# B_PITCHROLLER.net
KiCad netlist of a schematic drawn in Altium Designer
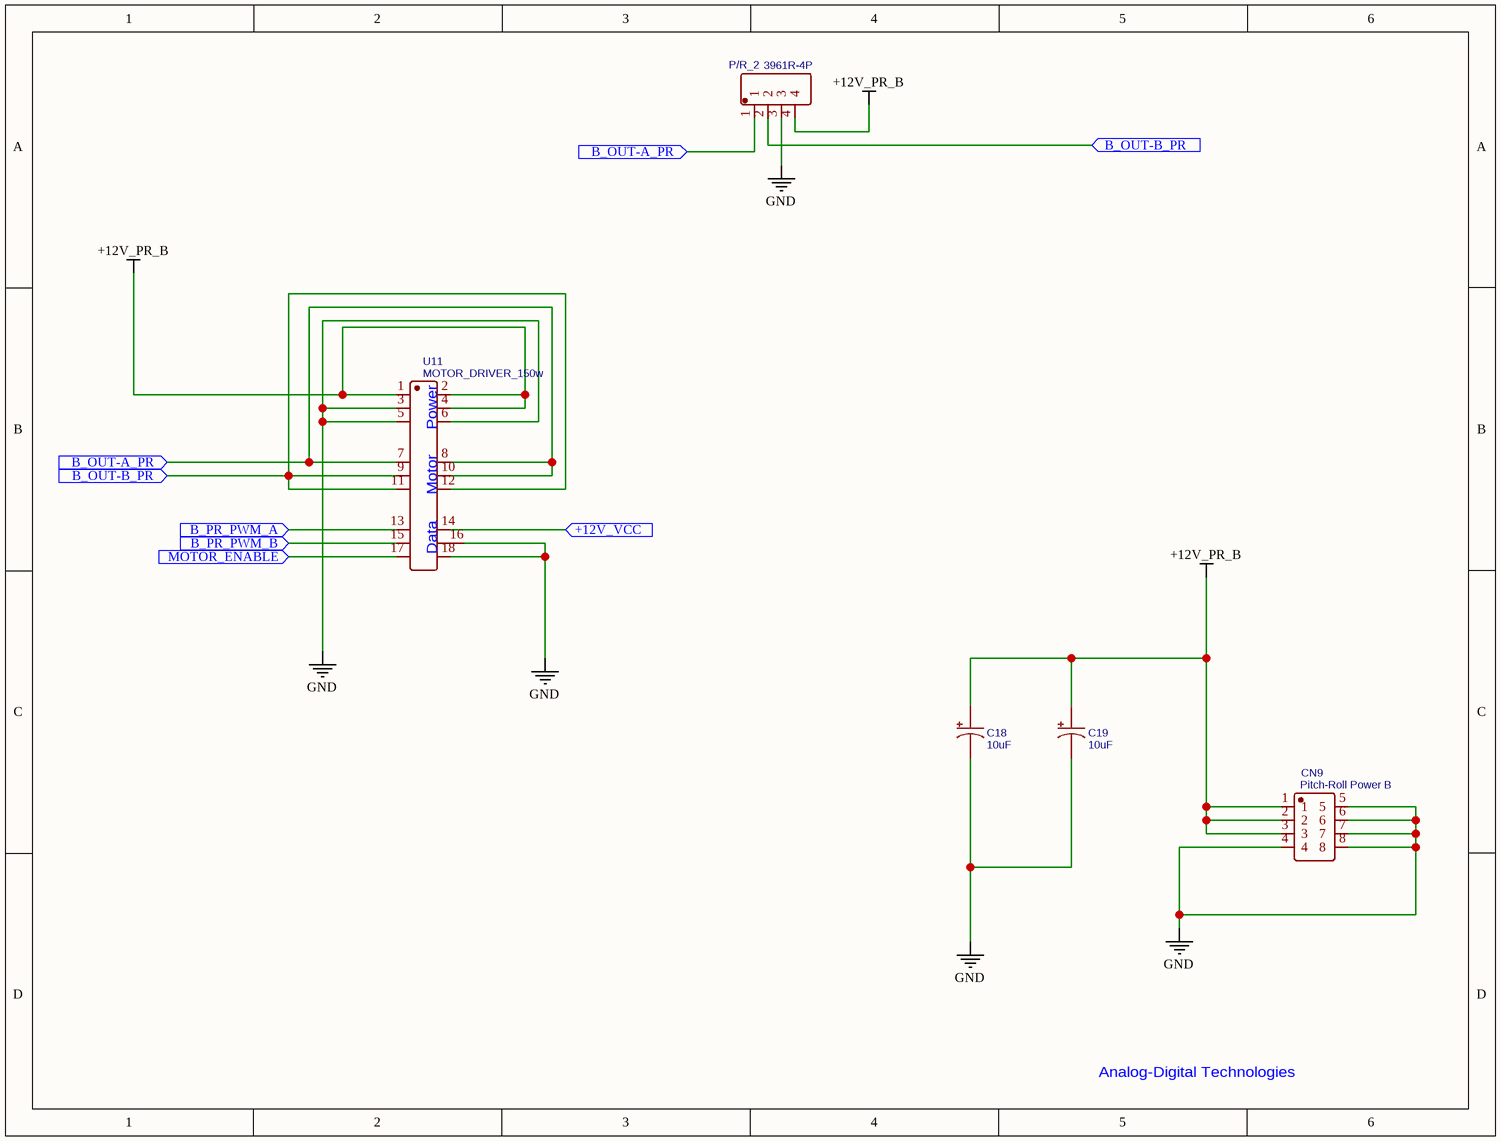
[diagram p0: B_PITCHROLLER.schdoc]

(export (version "E")
  (design (tool "Eeschema 10.0.6"))
  (components
    (comp (ref "C18")
      (value "10uF")
      (fields
        (field (name "BOM_SUPPLIER PART") "C213486")
        (field (name "BOM_MANUFACTURER PART") "VT1E100M0405")
        (field (name "CONTRIBUTOR") "LCSC")
      )
      (libsource (lib "altium-import") (part "root_1_10uF_"))
    )
    (comp (ref "C19")
      (value "10uF")
      (fields
        (field (name "BOM_SUPPLIER PART") "C213486")
        (field (name "BOM_MANUFACTURER PART") "VT1E100M0405")
        (field (name "CONTRIBUTOR") "LCSC")
      )
      (libsource (lib "altium-import") (part "root_1_10uF_"))
    )
    (comp (ref "CN9")
      (value "Pitch-Roll Power B")
      (fields
        (field (name "BOM_SUPPLIER PART") "C519240")
        (field (name "BOM_MANUFACTURER PART") "X9357WV-2*04-N2SN")
        (field (name "CONTRIBUTOR") "LCSC")
      )
      (libsource (lib "altium-import") (part "root_0_Pitch-Roll Power B_"))
    )
    (comp (ref "P/R_2")
      (value "3961R-4P")
      (fields (field (name "BOM_SUPPLIER PART") "C138427") (field (name "CONTRIBUTOR") "LCSC"))
      (libsource (lib "altium-import") (part "root_1_3961R-4P_"))
    )
    (comp (ref "U11")
      (value "MOTOR_DRIVER_150w")
      (fields (field (name "CONTRIBUTOR") "digitalman"))
      (libsource (lib "altium-import") (part "root_3_MOTOR_DRIVER_150w_"))
    )
  )
  (nets
    (net (code "1") (name "+12V_PR_B") (class "Default")
      (node (ref "C18") (pin "1") (pinfunction "1_1") (pintype "passive"))
      (node (ref "C19") (pin "1") (pinfunction "1_1") (pintype "passive"))
      (node (ref "CN9") (pin "1") (pinfunction "1_1") (pintype "passive"))
      (node (ref "CN9") (pin "2") (pinfunction "2_2") (pintype "passive"))
      (node (ref "CN9") (pin "3") (pinfunction "3_3") (pintype "passive"))
      (node (ref "P/R_2") (pin "4") (pinfunction "4_4") (pintype "passive"))
      (node (ref "U11") (pin "1") (pinfunction "+12V_YAW_1") (pintype "passive"))
      (node (ref "U11") (pin "2") (pinfunction "+12V_YAW_2") (pintype "passive"))
      (node (ref "U11") (pin "4") (pinfunction "+12V_YAW_4") (pintype "passive"))
    )
    (net (code "2") (name "/+12V_VCC") (class "Default")
      (node (ref "U11") (pin "14") (pinfunction "+12V_VCC_14") (pintype "passive"))
    )
    (net (code "3") (name "/B_OUT-A_PR") (class "Default")
      (node (ref "P/R_2") (pin "1") (pinfunction "1_1") (pintype "passive"))
      (node (ref "U11") (pin "10") (pinfunction "OUT-A_YAW_10") (pintype "passive"))
      (node (ref "U11") (pin "7") (pinfunction "OUT-A_YAW_7") (pintype "passive"))
      (node (ref "U11") (pin "8") (pinfunction "OUT-A_YAW_8") (pintype "passive"))
    )
    (net (code "4") (name "/B_OUT-B_PR") (class "Default")
      (node (ref "P/R_2") (pin "2") (pinfunction "2_2") (pintype "passive"))
      (node (ref "U11") (pin "11") (pinfunction "OUT-B_YAW_11") (pintype "passive"))
      (node (ref "U11") (pin "12") (pinfunction "OUT-B_YAW_12") (pintype "passive"))
      (node (ref "U11") (pin "9") (pinfunction "OUT-B_YAW_9") (pintype "passive"))
    )
    (net (code "5") (name "/B_PR_PWM_A") (class "Default")
      (node (ref "U11") (pin "13") (pinfunction "PWM-A_YAW_13") (pintype "passive"))
    )
    (net (code "6") (name "/B_PR_PWM_B") (class "Default")
      (node (ref "U11") (pin "15") (pinfunction "PWM-B_YAW_15") (pintype "passive"))
    )
    (net (code "7") (name "/MOTOR_ENABLE") (class "Default")
      (node (ref "U11") (pin "17") (pinfunction "MOTOR_ENABLE_17") (pintype "passive"))
    )
    (net (code "8") (name "GND") (class "Default")
      (node (ref "C18") (pin "2") (pinfunction "2_2") (pintype "passive"))
      (node (ref "C19") (pin "2") (pinfunction "2_2") (pintype "passive"))
      (node (ref "CN9") (pin "4") (pinfunction "4_4") (pintype "passive"))
      (node (ref "CN9") (pin "5") (pinfunction "5_5") (pintype "passive"))
      (node (ref "CN9") (pin "6") (pinfunction "6_6") (pintype "passive"))
      (node (ref "CN9") (pin "7") (pinfunction "7_7") (pintype "passive"))
      (node (ref "CN9") (pin "8") (pinfunction "8_8") (pintype "passive"))
      (node (ref "P/R_2") (pin "3") (pinfunction "3_3") (pintype "passive"))
      (node (ref "U11") (pin "16") (pinfunction "GND_16") (pintype "passive"))
      (node (ref "U11") (pin "18") (pinfunction "GND_18") (pintype "passive"))
      (node (ref "U11") (pin "3") (pinfunction "GND_3") (pintype "passive"))
      (node (ref "U11") (pin "5") (pinfunction "GND_5") (pintype "passive"))
      (node (ref "U11") (pin "6") (pinfunction "GND_6") (pintype "passive"))
    )
  )
)
